# 4_3_MCU_RGB.net
KiCad netlist of a schematic drawn in Altium Designer
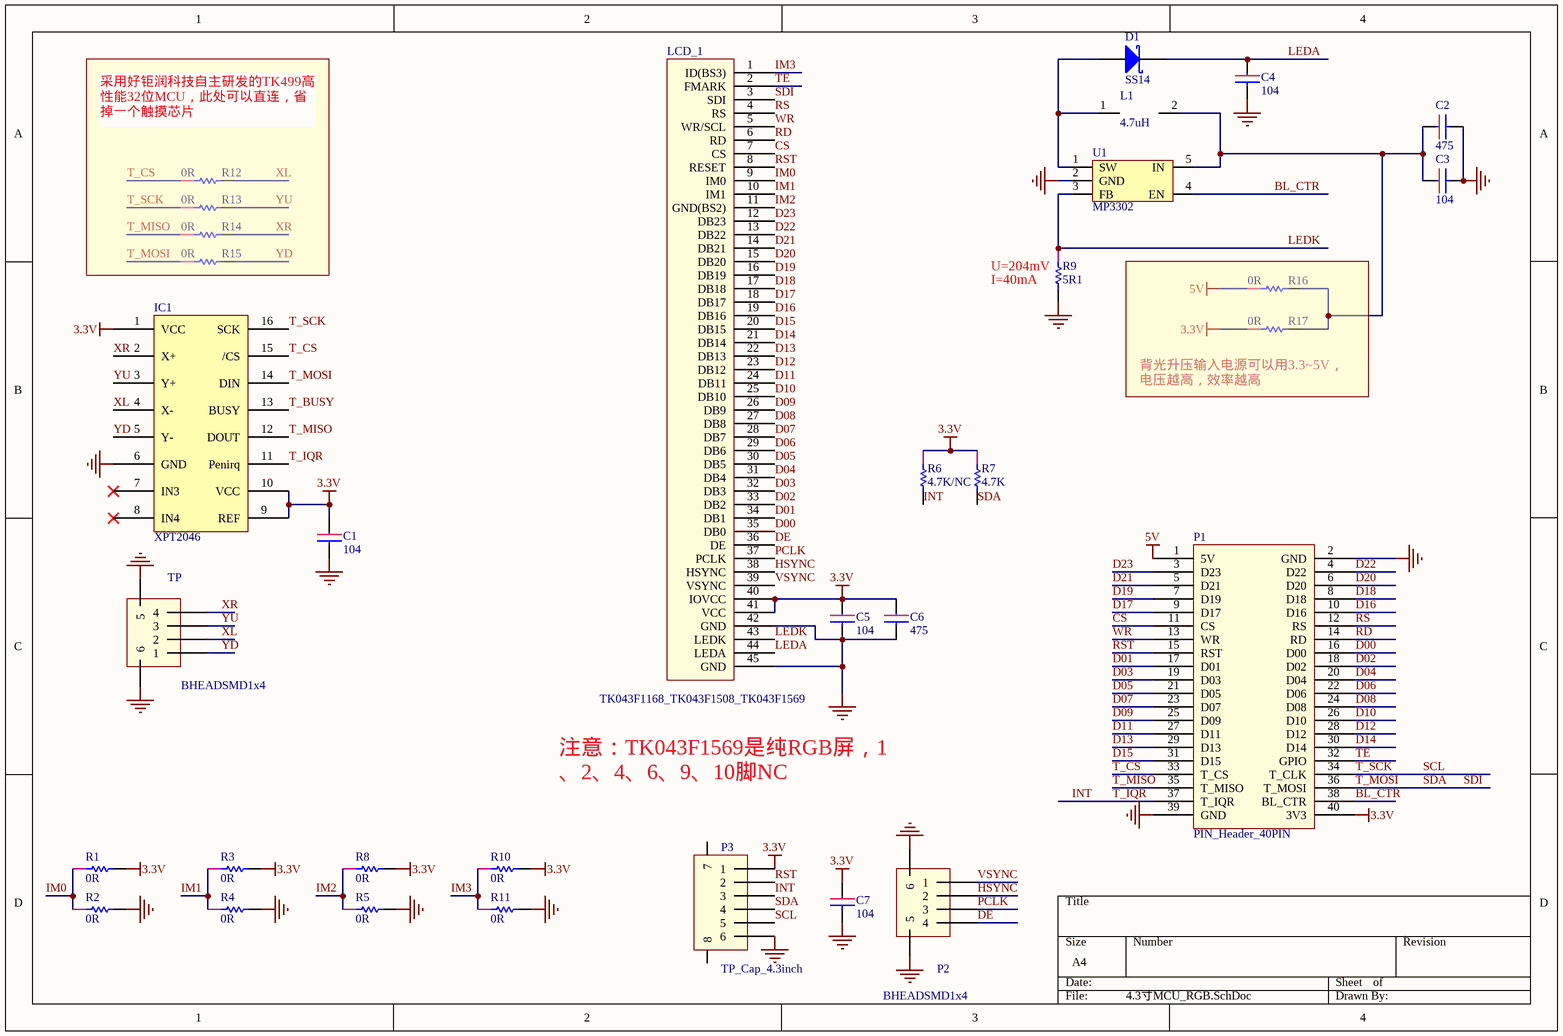
[diagram p0: 4.3寸MCU_RGB.SchDoc]

(export (version "E")
  (design (tool "Eeschema 10.0.6"))
  (components
    (comp (ref "C1") (value "104") (footprint "C0603-1") (libsource (lib "Tiky") (part "cap")))
    (comp (ref "C2") (value "475") (footprint "C0603-2") (libsource (lib "Tiky") (part "cap")))
    (comp (ref "C3") (value "104") (footprint "C0603-1") (libsource (lib "Tiky") (part "cap")))
    (comp (ref "C4") (value "104") (footprint "C0603-2") (libsource (lib "Tiky") (part "cap")))
    (comp (ref "C5") (value "104") (footprint "C0603-1") (libsource (lib "Tiky") (part "cap")))
    (comp (ref "C6") (value "475") (footprint "C0603-2") (libsource (lib "Tiky") (part "cap")))
    (comp (ref "C7") (value "104") (footprint "C0603-1") (libsource (lib "Tiky") (part "cap")))
    (comp (ref "D1")
      (value "SS14")
      (footprint "SOD123")
      (description "Schottky Diode")
      (fields (field (name "PUBLISHER") "Altium Limited"))
      (libsource (lib "Miscellaneous Devices") (part "D Schottky"))
    )
    (comp (ref "IC1") (value "XPT2046") (footprint "SOT403-1") (libsource (lib "Tiky") (part "ADS7843")))
    (comp (ref "L1") (value "4.7uH") (footprint "L1206") (libsource (lib "Tiky") (part "Inductor")))
    (comp (ref "LCD_1")
      (value "TK043F1168_TK043F1508_TK043F1569")
      (footprint "TFT_KGM1066A0")
      (libsource (lib "Tiky") (part "TK043F1168"))
    )
    (comp (ref "P1")
      (value "PIN_Header_40PIN")
      (footprint "P_Head_2x20")
      (libsource (lib "Tiky") (part "PIN_Header_40PIN"))
    )
    (comp (ref "P2")
      (value "BHEADSMD1x4")
      (footprint "BHEADSMD1x4")
      (libsource (lib "Tiky") (part "BHEADSMD1x4"))
    )
    (comp (ref "P3")
      (value "TP_Cap_4.3inch")
      (footprint "TP_Cap_4.3inch")
      (libsource (lib "Tiky") (part "BHEADSMD1x6"))
    )
    (comp (ref "R1") (value "0R") (footprint "R0603") (libsource (lib "Tiky") (part "Resistor")))
    (comp (ref "R2") (value "0R") (footprint "R0603") (libsource (lib "Tiky") (part "Resistor")))
    (comp (ref "R3") (value "0R") (footprint "R0603") (libsource (lib "Tiky") (part "Resistor")))
    (comp (ref "R4") (value "0R") (footprint "R0603") (libsource (lib "Tiky") (part "Resistor")))
    (comp (ref "R5") (value "0R") (footprint "R0603") (libsource (lib "Tiky") (part "Resistor")))
    (comp (ref "R6") (value "4.7K/NC") (footprint "R0603") (libsource (lib "Tiky") (part "Resistor")))
    (comp (ref "R7") (value "4.7K") (footprint "R0603") (libsource (lib "Tiky") (part "Resistor")))
    (comp (ref "R8") (value "0R") (footprint "R0603") (libsource (lib "Tiky") (part "Resistor")))
    (comp (ref "R9") (value "5R1") (footprint "R0603") (libsource (lib "Tiky") (part "Resistor")))
    (comp (ref "R10") (value "0R") (footprint "R0603") (libsource (lib "Tiky") (part "Resistor")))
    (comp (ref "R11") (value "0R") (footprint "R0603") (libsource (lib "Tiky") (part "Resistor")))
    (comp (ref "R12") (value "0R") (footprint "R0402") (libsource (lib "Tiky") (part "Resistor")))
    (comp (ref "R13") (value "0R") (footprint "R0402") (libsource (lib "Tiky") (part "Resistor")))
    (comp (ref "R14") (value "0R") (footprint "R0402") (libsource (lib "Tiky") (part "Resistor")))
    (comp (ref "R15") (value "0R") (footprint "R0402") (libsource (lib "Tiky") (part "Resistor")))
    (comp (ref "R16") (value "0R") (footprint "R0402") (libsource (lib "Tiky") (part "Resistor")))
    (comp (ref "R17") (value "0R") (footprint "R0402") (libsource (lib "Tiky") (part "Resistor")))
    (comp (ref "TP")
      (value "BHEADSMD1x4")
      (footprint "TP_5.0inch")
      (libsource (lib "") (part "BHEADSMD1x4_1"))
    )
    (comp (ref "U1") (value "MP3302") (footprint "SOT23-5") (libsource (lib "Tiky") (part "MP3302")))
  )
  (nets
    (net (code "1") (name "/BL_CTR") (class "Default")
      (node (ref "P1") (pin "38") (pinfunction "BL_CTR_38") (pintype "passive"))
      (node (ref "U1") (pin "4") (pinfunction "EN_4") (pintype "passive"))
    )
    (net (code "2") (name "/CS") (class "Default")
      (node (ref "LCD_1") (pin "7") (pinfunction "CS_7") (pintype "passive"))
      (node (ref "P1") (pin "11") (pinfunction "CS_11") (pintype "passive"))
    )
    (net (code "3") (name "/D00") (class "Default")
      (node (ref "LCD_1") (pin "35") (pinfunction "DB0_35") (pintype "passive"))
      (node (ref "P1") (pin "16") (pinfunction "D00_16") (pintype "passive"))
    )
    (net (code "4") (name "/D01") (class "Default")
      (node (ref "LCD_1") (pin "34") (pinfunction "DB1_34") (pintype "passive"))
      (node (ref "P1") (pin "17") (pinfunction "D01_17") (pintype "passive"))
    )
    (net (code "5") (name "/D02") (class "Default")
      (node (ref "LCD_1") (pin "33") (pinfunction "DB2_33") (pintype "passive"))
      (node (ref "P1") (pin "18") (pinfunction "D02_18") (pintype "passive"))
    )
    (net (code "6") (name "/D03") (class "Default")
      (node (ref "LCD_1") (pin "32") (pinfunction "DB3_32") (pintype "passive"))
      (node (ref "P1") (pin "19") (pinfunction "D03_19") (pintype "passive"))
    )
    (net (code "7") (name "/D04") (class "Default")
      (node (ref "LCD_1") (pin "31") (pinfunction "DB4_31") (pintype "passive"))
      (node (ref "P1") (pin "20") (pinfunction "D04_20") (pintype "passive"))
    )
    (net (code "8") (name "/D05") (class "Default")
      (node (ref "LCD_1") (pin "30") (pinfunction "DB5_30") (pintype "passive"))
      (node (ref "P1") (pin "21") (pinfunction "D05_21") (pintype "passive"))
    )
    (net (code "9") (name "/D06") (class "Default")
      (node (ref "LCD_1") (pin "29") (pinfunction "DB6_29") (pintype "passive"))
      (node (ref "P1") (pin "22") (pinfunction "D06_22") (pintype "passive"))
    )
    (net (code "10") (name "/D07") (class "Default")
      (node (ref "LCD_1") (pin "28") (pinfunction "DB7_28") (pintype "passive"))
      (node (ref "P1") (pin "23") (pinfunction "D07_23") (pintype "passive"))
    )
    (net (code "11") (name "/D08") (class "Default")
      (node (ref "LCD_1") (pin "27") (pinfunction "DB8_27") (pintype "passive"))
      (node (ref "P1") (pin "24") (pinfunction "D08_24") (pintype "passive"))
    )
    (net (code "12") (name "/D09") (class "Default")
      (node (ref "LCD_1") (pin "26") (pinfunction "DB9_26") (pintype "passive"))
      (node (ref "P1") (pin "25") (pinfunction "D09_25") (pintype "passive"))
    )
    (net (code "13") (name "/D10") (class "Default")
      (node (ref "LCD_1") (pin "25") (pinfunction "DB10_25") (pintype "passive"))
      (node (ref "P1") (pin "26") (pinfunction "D10_26") (pintype "passive"))
    )
    (net (code "14") (name "/D11") (class "Default")
      (node (ref "LCD_1") (pin "24") (pinfunction "DB11_24") (pintype "passive"))
      (node (ref "P1") (pin "27") (pinfunction "D11_27") (pintype "passive"))
    )
    (net (code "15") (name "/D12") (class "Default")
      (node (ref "LCD_1") (pin "23") (pinfunction "DB12_23") (pintype "passive"))
      (node (ref "P1") (pin "28") (pinfunction "D12_28") (pintype "passive"))
    )
    (net (code "16") (name "/D13") (class "Default")
      (node (ref "LCD_1") (pin "22") (pinfunction "DB13_22") (pintype "passive"))
      (node (ref "P1") (pin "29") (pinfunction "D13_29") (pintype "passive"))
    )
    (net (code "17") (name "/D14") (class "Default")
      (node (ref "LCD_1") (pin "21") (pinfunction "DB14_21") (pintype "passive"))
      (node (ref "P1") (pin "30") (pinfunction "D14_30") (pintype "passive"))
    )
    (net (code "18") (name "/D15") (class "Default")
      (node (ref "LCD_1") (pin "20") (pinfunction "DB15_20") (pintype "passive"))
      (node (ref "P1") (pin "31") (pinfunction "D15_31") (pintype "passive"))
    )
    (net (code "19") (name "/D16") (class "Default")
      (node (ref "LCD_1") (pin "19") (pinfunction "DB16_19") (pintype "passive"))
      (node (ref "P1") (pin "10") (pinfunction "D16_10") (pintype "passive"))
    )
    (net (code "20") (name "/D17") (class "Default")
      (node (ref "LCD_1") (pin "18") (pinfunction "DB17_18") (pintype "passive"))
      (node (ref "P1") (pin "9") (pinfunction "D17_9") (pintype "passive"))
    )
    (net (code "21") (name "/D18") (class "Default")
      (node (ref "LCD_1") (pin "17") (pinfunction "DB18_17") (pintype "passive"))
      (node (ref "P1") (pin "8") (pinfunction "D18_8") (pintype "passive"))
    )
    (net (code "22") (name "/D19") (class "Default")
      (node (ref "LCD_1") (pin "16") (pinfunction "DB19_16") (pintype "passive"))
      (node (ref "P1") (pin "7") (pinfunction "D19_7") (pintype "passive"))
    )
    (net (code "23") (name "/D20") (class "Default")
      (node (ref "LCD_1") (pin "15") (pinfunction "DB20_15") (pintype "passive"))
      (node (ref "P1") (pin "6") (pinfunction "D20_6") (pintype "passive"))
    )
    (net (code "24") (name "/D21") (class "Default")
      (node (ref "LCD_1") (pin "14") (pinfunction "DB21_14") (pintype "passive"))
      (node (ref "P1") (pin "5") (pinfunction "D21_5") (pintype "passive"))
    )
    (net (code "25") (name "/D22") (class "Default")
      (node (ref "LCD_1") (pin "13") (pinfunction "DB22_13") (pintype "passive"))
      (node (ref "P1") (pin "4") (pinfunction "D22_4") (pintype "passive"))
    )
    (net (code "26") (name "/D23") (class "Default")
      (node (ref "LCD_1") (pin "12") (pinfunction "DB23_12") (pintype "passive"))
      (node (ref "P1") (pin "3") (pinfunction "D23_3") (pintype "passive"))
    )
    (net (code "27") (name "/DE") (class "Default")
      (node (ref "LCD_1") (pin "36") (pinfunction "DE_36") (pintype "passive"))
      (node (ref "P2") (pin "4") (pinfunction "4_4") (pintype "passive"))
    )
    (net (code "28") (name "/HSYNC") (class "Default")
      (node (ref "LCD_1") (pin "38") (pinfunction "HSYNC_38") (pintype "passive"))
      (node (ref "P2") (pin "2") (pinfunction "2_2") (pintype "passive"))
    )
    (net (code "29") (name "/IM0") (class "Default")
      (node (ref "LCD_1") (pin "9") (pinfunction "IM0_9") (pintype "passive"))
      (node (ref "R1") (pin "1") (pinfunction "1_1") (pintype "passive"))
      (node (ref "R2") (pin "1") (pinfunction "1_1") (pintype "passive"))
    )
    (net (code "30") (name "/IM1") (class "Default")
      (node (ref "LCD_1") (pin "10") (pinfunction "IM1_10") (pintype "passive"))
      (node (ref "R3") (pin "1") (pinfunction "1_1") (pintype "passive"))
      (node (ref "R4") (pin "1") (pinfunction "1_1") (pintype "passive"))
    )
    (net (code "31") (name "/IM2") (class "Default")
      (node (ref "LCD_1") (pin "11") (pinfunction "GND(BS2)_11") (pintype "passive"))
      (node (ref "R5") (pin "1") (pinfunction "1_1") (pintype "passive"))
      (node (ref "R8") (pin "1") (pinfunction "1_1") (pintype "passive"))
    )
    (net (code "32") (name "/IM3") (class "Default")
      (node (ref "LCD_1") (pin "1") (pinfunction "ID(BS3)_1") (pintype "passive"))
      (node (ref "R10") (pin "1") (pinfunction "1_1") (pintype "passive"))
      (node (ref "R11") (pin "1") (pinfunction "1_1") (pintype "passive"))
    )
    (net (code "33") (name "/INT") (class "Default")
      (node (ref "IC1") (pin "11") (pinfunction "Penirq_11") (pintype "passive"))
      (node (ref "P1") (pin "37") (pinfunction "T_IQR_37") (pintype "passive"))
      (node (ref "P3") (pin "3") (pinfunction "3_3") (pintype "passive"))
      (node (ref "R6") (pin "2") (pinfunction "2_2") (pintype "passive"))
    )
    (net (code "34") (name "/LEDA") (class "Default")
      (node (ref "C4") (pin "1") (pinfunction "1_1") (pintype "passive"))
      (node (ref "D1") (pin "2") (pinfunction "K_2") (pintype "passive"))
      (node (ref "LCD_1") (pin "44") (pinfunction "LEDA_44") (pintype "passive"))
    )
    (net (code "35") (name "/LEDK") (class "Default")
      (node (ref "LCD_1") (pin "43") (pinfunction "LEDK_43") (pintype "passive"))
      (node (ref "R9") (pin "1") (pinfunction "1_1") (pintype "passive"))
      (node (ref "U1") (pin "3") (pinfunction "FB_3") (pintype "passive"))
    )
    (net (code "36") (name "/PCLK") (class "Default")
      (node (ref "LCD_1") (pin "37") (pinfunction "PCLK_37") (pintype "passive"))
      (node (ref "P2") (pin "3") (pinfunction "3_3") (pintype "passive"))
    )
    (net (code "37") (name "/RD") (class "Default")
      (node (ref "LCD_1") (pin "6") (pinfunction "RD_6") (pintype "passive"))
      (node (ref "P1") (pin "14") (pinfunction "RD_14") (pintype "passive"))
    )
    (net (code "38") (name "/RS") (class "Default")
      (node (ref "LCD_1") (pin "4") (pinfunction "RS_4") (pintype "passive"))
      (node (ref "P1") (pin "12") (pinfunction "RS_12") (pintype "passive"))
    )
    (net (code "39") (name "/RST") (class "Default")
      (node (ref "LCD_1") (pin "8") (pinfunction "RESET_8") (pintype "passive"))
      (node (ref "P1") (pin "15") (pinfunction "RST_15") (pintype "passive"))
      (node (ref "P3") (pin "2") (pinfunction "2_2") (pintype "passive"))
    )
    (net (code "40") (name "/SCL") (class "Default")
      (node (ref "IC1") (pin "16") (pinfunction "SCK_16") (pintype "passive"))
      (node (ref "P1") (pin "34") (pinfunction "T_CLK_34") (pintype "passive"))
      (node (ref "P3") (pin "5") (pinfunction "5_5") (pintype "passive"))
      (node (ref "R13") (pin "1") (pinfunction "1_1") (pintype "passive"))
    )
    (net (code "41") (name "/SDA") (class "Default")
      (node (ref "IC1") (pin "14") (pinfunction "DIN_14") (pintype "passive"))
      (node (ref "LCD_1") (pin "3") (pinfunction "SDI_3") (pintype "passive"))
      (node (ref "P1") (pin "36") (pinfunction "T_MOSI_36") (pintype "passive"))
      (node (ref "P3") (pin "4") (pinfunction "4_4") (pintype "passive"))
      (node (ref "R15") (pin "1") (pinfunction "1_1") (pintype "passive"))
      (node (ref "R7") (pin "2") (pinfunction "2_2") (pintype "passive"))
    )
    (net (code "42") (name "/TE") (class "Default")
      (node (ref "LCD_1") (pin "2") (pinfunction "FMARK_2") (pintype "passive"))
      (node (ref "P1") (pin "32") (pinfunction "GPIO_32") (pintype "passive"))
    )
    (net (code "43") (name "/T_BUSY") (class "Default")
      (node (ref "IC1") (pin "13") (pinfunction "BUSY_13") (pintype "passive"))
    )
    (net (code "44") (name "/T_CS") (class "Default")
      (node (ref "IC1") (pin "15") (pinfunction "/CS_15") (pintype "passive"))
      (node (ref "P1") (pin "33") (pinfunction "T_CS_33") (pintype "passive"))
      (node (ref "R12") (pin "1") (pinfunction "1_1") (pintype "passive"))
    )
    (net (code "45") (name "/T_MISO") (class "Default")
      (node (ref "IC1") (pin "12") (pinfunction "DOUT_12") (pintype "passive"))
      (node (ref "P1") (pin "35") (pinfunction "T_MISO_35") (pintype "passive"))
      (node (ref "R14") (pin "1") (pinfunction "1_1") (pintype "passive"))
    )
    (net (code "46") (name "/VSYNC") (class "Default")
      (node (ref "LCD_1") (pin "39") (pinfunction "VSYNC_39") (pintype "passive"))
      (node (ref "P2") (pin "1") (pinfunction "1_1") (pintype "passive"))
    )
    (net (code "47") (name "/WR") (class "Default")
      (node (ref "LCD_1") (pin "5") (pinfunction "WR/SCL_5") (pintype "passive"))
      (node (ref "P1") (pin "13") (pinfunction "WR_13") (pintype "passive"))
    )
    (net (code "48") (name "/XL") (class "Default")
      (node (ref "IC1") (pin "4") (pinfunction "X-_4") (pintype "passive"))
      (node (ref "R12") (pin "2") (pinfunction "2_2") (pintype "passive"))
      (node (ref "TP") (pin "2") (pinfunction "2_2") (pintype "passive"))
    )
    (net (code "49") (name "/XR") (class "Default")
      (node (ref "IC1") (pin "2") (pinfunction "X+_2") (pintype "passive"))
      (node (ref "R14") (pin "2") (pinfunction "2_2") (pintype "passive"))
      (node (ref "TP") (pin "4") (pinfunction "4_4") (pintype "passive"))
    )
    (net (code "50") (name "/YD") (class "Default")
      (node (ref "IC1") (pin "5") (pinfunction "Y-_5") (pintype "passive"))
      (node (ref "R15") (pin "2") (pinfunction "2_2") (pintype "passive"))
      (node (ref "TP") (pin "1") (pinfunction "1_1") (pintype "passive"))
    )
    (net (code "51") (name "/YU") (class "Default")
      (node (ref "IC1") (pin "3") (pinfunction "Y+_3") (pintype "passive"))
      (node (ref "R13") (pin "2") (pinfunction "2_2") (pintype "passive"))
      (node (ref "TP") (pin "3") (pinfunction "3_3") (pintype "passive"))
    )
    (net (code "52") (name "3.3V") (class "Default")
      (node (ref "C1") (pin "1") (pinfunction "1_1") (pintype "passive"))
      (node (ref "C5") (pin "1") (pinfunction "1_1") (pintype "passive"))
      (node (ref "C6") (pin "1") (pinfunction "1_1") (pintype "passive"))
      (node (ref "C7") (pin "1") (pinfunction "1_1") (pintype "passive"))
      (node (ref "IC1") (pin "1") (pinfunction "VCC_1") (pintype "passive"))
      (node (ref "IC1") (pin "10") (pinfunction "VCC_10") (pintype "passive"))
      (node (ref "IC1") (pin "9") (pinfunction "REF_9") (pintype "passive"))
      (node (ref "LCD_1") (pin "40") (pinfunction "IOVCC_40") (pintype "passive"))
      (node (ref "LCD_1") (pin "41") (pinfunction "VCC_41") (pintype "passive"))
      (node (ref "P1") (pin "40") (pinfunction "3V3_40") (pintype "passive"))
      (node (ref "P3") (pin "1") (pinfunction "1_1") (pintype "passive"))
      (node (ref "R1") (pin "2") (pinfunction "2_2") (pintype "passive"))
      (node (ref "R10") (pin "2") (pinfunction "2_2") (pintype "passive"))
      (node (ref "R17") (pin "1") (pinfunction "1_1") (pintype "passive"))
      (node (ref "R3") (pin "2") (pinfunction "2_2") (pintype "passive"))
      (node (ref "R6") (pin "1") (pinfunction "1_1") (pintype "passive"))
      (node (ref "R7") (pin "1") (pinfunction "1_1") (pintype "passive"))
      (node (ref "R8") (pin "2") (pinfunction "2_2") (pintype "passive"))
    )
    (net (code "53") (name "5V") (class "Default")
      (node (ref "P1") (pin "1") (pinfunction "5V_1") (pintype "passive"))
      (node (ref "R16") (pin "1") (pinfunction "1_1") (pintype "passive"))
    )
    (net (code "54") (name "GND") (class "Default")
      (node (ref "C1") (pin "2") (pinfunction "2_2") (pintype "passive"))
      (node (ref "C2") (pin "2") (pinfunction "2_2") (pintype "passive"))
      (node (ref "C3") (pin "2") (pinfunction "2_2") (pintype "passive"))
      (node (ref "C4") (pin "2") (pinfunction "2_2") (pintype "passive"))
      (node (ref "C5") (pin "2") (pinfunction "2_2") (pintype "passive"))
      (node (ref "C6") (pin "2") (pinfunction "2_2") (pintype "passive"))
      (node (ref "C7") (pin "2") (pinfunction "2_2") (pintype "passive"))
      (node (ref "IC1") (pin "6") (pinfunction "GND_6") (pintype "passive"))
      (node (ref "LCD_1") (pin "42") (pinfunction "GND_42") (pintype "passive"))
      (node (ref "LCD_1") (pin "45") (pinfunction "GND_45") (pintype "passive"))
      (node (ref "P1") (pin "2") (pinfunction "GND_2") (pintype "passive"))
      (node (ref "P1") (pin "39") (pinfunction "GND_39") (pintype "passive"))
      (node (ref "P2") (pin "5") (pinfunction "5_5") (pintype "passive"))
      (node (ref "P2") (pin "6") (pinfunction "6_6") (pintype "passive"))
      (node (ref "P3") (pin "6") (pinfunction "6_6") (pintype "passive"))
      (node (ref "R11") (pin "2") (pinfunction "2_2") (pintype "passive"))
      (node (ref "R2") (pin "2") (pinfunction "2_2") (pintype "passive"))
      (node (ref "R4") (pin "2") (pinfunction "2_2") (pintype "passive"))
      (node (ref "R5") (pin "2") (pinfunction "2_2") (pintype "passive"))
      (node (ref "R9") (pin "2") (pinfunction "2_2") (pintype "passive"))
      (node (ref "TP") (pin "5") (pinfunction "5_5") (pintype "passive"))
      (node (ref "TP") (pin "6") (pinfunction "6_6") (pintype "passive"))
      (node (ref "U1") (pin "2") (pinfunction "GND_2") (pintype "passive"))
    )
    (net (code "55") (name "Net-(D1-A)") (class "Default")
      (node (ref "D1") (pin "1") (pinfunction "A_1") (pintype "passive"))
      (node (ref "L1") (pin "1") (pinfunction "1_1") (pintype "passive"))
      (node (ref "U1") (pin "1") (pinfunction "SW_1") (pintype "passive"))
    )
    (net (code "56") (name "Net-(U1-IN)") (class "Default")
      (node (ref "C2") (pin "1") (pinfunction "1_1") (pintype "passive"))
      (node (ref "C3") (pin "1") (pinfunction "1_1") (pintype "passive"))
      (node (ref "L1") (pin "2") (pinfunction "2_2") (pintype "passive"))
      (node (ref "R16") (pin "2") (pinfunction "2_2") (pintype "passive"))
      (node (ref "R17") (pin "2") (pinfunction "2_2") (pintype "passive"))
      (node (ref "U1") (pin "5") (pinfunction "IN_5") (pintype "passive"))
    )
    (net (code "57") (name "unconnected-(IC1-IN3-Pad7)") (class "Default")
      (node (ref "IC1") (pin "7") (pinfunction "IN3_7") (pintype "passive+no_connect"))
    )
    (net (code "58") (name "unconnected-(IC1-IN4-Pad8)") (class "Default")
      (node (ref "IC1") (pin "8") (pinfunction "IN4_8") (pintype "passive+no_connect"))
    )
    (net (code "59") (name "unconnected-(P3-Pad7)") (class "Default")
      (node (ref "P3") (pin "7") (pinfunction "7_7") (pintype "passive"))
    )
    (net (code "60") (name "unconnected-(P3-Pad8)") (class "Default")
      (node (ref "P3") (pin "8") (pinfunction "8_8") (pintype "passive"))
    )
  )
)
